# scd55104_chess_clock.net
KiCad netlist of a schematic drawn in EAGLE
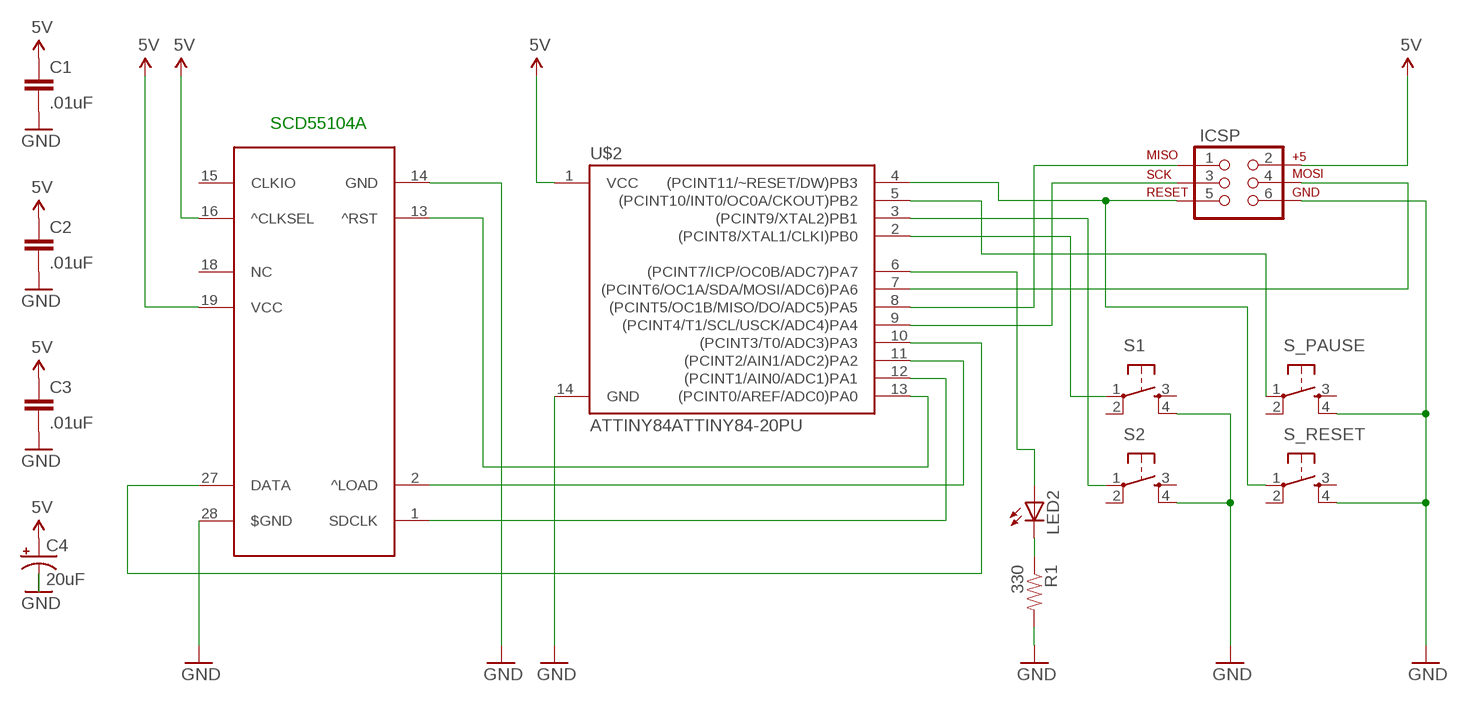
[diagram p0: schematic, sheet 1]

(export (version "E")
  (design (tool "Eeschema 10.0.6"))
  (components
    (comp (ref "C1")
      (value ".01uF")
      (footprint "eagle-import:CAP-PTH-SMALL")
      (libsource (lib "eagle-import") (part "CAPPTH"))
    )
    (comp (ref "C2")
      (value ".01uF")
      (footprint "eagle-import:CAP-PTH-SMALL")
      (libsource (lib "eagle-import") (part "CAPPTH"))
    )
    (comp (ref "C3")
      (value ".01uF")
      (footprint "eagle-import:CAP-PTH-SMALL")
      (libsource (lib "eagle-import") (part "CAPPTH"))
    )
    (comp (ref "C4")
      (value "20uF")
      (footprint "eagle-import:CPOL-RADIAL-10UF-25V")
      (libsource (lib "eagle-import") (part "CAP_POLPTH2"))
    )
    (comp (ref "ICSP")
      (value "AVR_SPI_PRG_6PTH")
      (footprint "eagle-import:2X3")
      (libsource (lib "eagle-import") (part "AVR_SPI_PRG_6PTH"))
    )
    (comp (ref "LED2")
      (value "LED3MM")
      (footprint "eagle-import:LED3MM")
      (libsource (lib "eagle-import") (part "LED3MM"))
    )
    (comp (ref "R1")
      (value "330")
      (footprint "eagle-import:AXIAL-0.4")
      (libsource (lib "eagle-import") (part "RESISTORPTH-1/4W"))
    )
    (comp (ref "S1")
      (value "TAC_SWITCHPTH")
      (footprint "eagle-import:TACTILE-PTH")
      (libsource (lib "eagle-import") (part "TAC_SWITCHPTH"))
    )
    (comp (ref "S2")
      (value "TAC_SWITCHPTH")
      (footprint "eagle-import:TACTILE-PTH")
      (libsource (lib "eagle-import") (part "TAC_SWITCHPTH"))
    )
    (comp (ref "SCD55104A")
      (value "SCD_55104A")
      (footprint "eagle-import:SCD55104A")
      (libsource (lib "eagle-import") (part "SCD_55104A"))
    )
    (comp (ref "S_PAUSE")
      (value "TAC_SWITCHPTH")
      (footprint "eagle-import:TACTILE-PTH")
      (libsource (lib "eagle-import") (part "TAC_SWITCHPTH"))
    )
    (comp (ref "S_RESET")
      (value "TAC_SWITCHPTH")
      (footprint "eagle-import:TACTILE-PTH")
      (libsource (lib "eagle-import") (part "TAC_SWITCHPTH"))
    )
    (comp (ref "U$2")
      (value "ATTINY84ATTINY84-20PU")
      (footprint "eagle-import:DIL14")
      (libsource (lib "eagle-import") (part "ATTINY84ATTINY84-20PU"))
    )
  )
  (nets
    (net (code "1") (name "5V") (class "Default")
      (node (ref "C1") (pin "1") (pinfunction "1_1") (pintype "passive"))
      (node (ref "C2") (pin "1") (pinfunction "1_1") (pintype "passive"))
      (node (ref "C3") (pin "1") (pinfunction "1_1") (pintype "passive"))
      (node (ref "C4") (pin "1") (pinfunction "+_1") (pintype "passive"))
      (node (ref "ICSP") (pin "2") (pinfunction "2_2") (pintype "passive"))
      (node (ref "SCD55104A") (pin "16") (pinfunction "^CLKSEL_16") (pintype "bidirectional"))
      (node (ref "SCD55104A") (pin "19") (pinfunction "VCC_19") (pintype "bidirectional"))
      (node (ref "U$2") (pin "1") (pinfunction "VCC_1") (pintype "bidirectional"))
    )
    (net (code "2") (name "GND") (class "Default")
      (node (ref "C1") (pin "2") (pinfunction "2_2") (pintype "passive"))
      (node (ref "C2") (pin "2") (pinfunction "2_2") (pintype "passive"))
      (node (ref "C3") (pin "2") (pinfunction "2_2") (pintype "passive"))
      (node (ref "C4") (pin "2") (pinfunction "-_2") (pintype "passive"))
      (node (ref "ICSP") (pin "6") (pinfunction "6_6") (pintype "passive"))
      (node (ref "R1") (pin "P$2") (pinfunction "2_P$2") (pintype "passive"))
      (node (ref "S1") (pin "4") (pinfunction "4_4") (pintype "passive"))
      (node (ref "S2") (pin "4") (pinfunction "4_4") (pintype "passive"))
      (node (ref "SCD55104A") (pin "14") (pinfunction "GND_14") (pintype "bidirectional"))
      (node (ref "SCD55104A") (pin "28") (pinfunction "$GND_28") (pintype "bidirectional"))
      (node (ref "S_PAUSE") (pin "4") (pinfunction "4_4") (pintype "passive"))
      (node (ref "S_RESET") (pin "4") (pinfunction "4_4") (pintype "passive"))
      (node (ref "U$2") (pin "14") (pinfunction "GND_14") (pintype "bidirectional"))
    )
    (net (code "3") (name "Net-(LED2-C)") (class "Default")
      (node (ref "LED2") (pin "K") (pinfunction "C_K") (pintype "passive"))
      (node (ref "R1") (pin "P$1") (pinfunction "1_P$1") (pintype "passive"))
    )
    (net (code "4") (name "Net-(SCD55104A-DATA)") (class "Default")
      (node (ref "SCD55104A") (pin "27") (pinfunction "DATA_27") (pintype "bidirectional"))
      (node (ref "U$2") (pin "10") (pinfunction "(PCINT3/T0/ADC3)PA3_10") (pintype "bidirectional"))
    )
    (net (code "5") (name "Net-(SCD55104A-SDCLK)") (class "Default")
      (node (ref "SCD55104A") (pin "1") (pinfunction "SDCLK_1") (pintype "bidirectional"))
      (node (ref "U$2") (pin "12") (pinfunction "(PCINT1/AIN0/ADC1)PA1_12") (pintype "bidirectional"))
    )
    (net (code "6") (name "Net-(SCD55104A-^LOAD)") (class "Default")
      (node (ref "SCD55104A") (pin "2") (pinfunction "^LOAD_2") (pintype "bidirectional"))
      (node (ref "U$2") (pin "11") (pinfunction "(PCINT2/AIN1/ADC2)PA2_11") (pintype "bidirectional"))
    )
    (net (code "7") (name "Net-(SCD55104A-^RST)") (class "Default")
      (node (ref "SCD55104A") (pin "13") (pinfunction "^RST_13") (pintype "bidirectional"))
      (node (ref "U$2") (pin "13") (pinfunction "(PCINT0/AREF/ADC0)PA0_13") (pintype "bidirectional"))
    )
    (net (code "8") (name "Net-(U$2-(PCINT4{slash}T1{slash}SCL{slash}USCK{slash}ADC4)PA4)") (class "Default")
      (node (ref "ICSP") (pin "3") (pinfunction "3_3") (pintype "passive"))
      (node (ref "U$2") (pin "9") (pinfunction "(PCINT4/T1/SCL/USCK/ADC4)PA4_9") (pintype "bidirectional"))
    )
    (net (code "9") (name "Net-(U$2-(PCINT5{slash}OC1B{slash}MISO{slash}DO{slash}ADC5)PA5)") (class "Default")
      (node (ref "ICSP") (pin "1") (pinfunction "1_1") (pintype "passive"))
      (node (ref "U$2") (pin "8") (pinfunction "(PCINT5/OC1B/MISO/DO/ADC5)PA5_8") (pintype "bidirectional"))
    )
    (net (code "10") (name "Net-(U$2-(PCINT6{slash}OC1A{slash}SDA{slash}MOSI{slash}ADC6)PA6)") (class "Default")
      (node (ref "ICSP") (pin "4") (pinfunction "4_4") (pintype "passive"))
      (node (ref "U$2") (pin "7") (pinfunction "(PCINT6/OC1A/SDA/MOSI/ADC6)PA6_7") (pintype "bidirectional"))
    )
    (net (code "11") (name "Net-(U$2-(PCINT7{slash}ICP{slash}OC0B{slash}ADC7)PA7)") (class "Default")
      (node (ref "LED2") (pin "A") (pinfunction "A_A") (pintype "passive"))
      (node (ref "U$2") (pin "6") (pinfunction "(PCINT7/ICP/OC0B/ADC7)PA7_6") (pintype "bidirectional"))
    )
    (net (code "12") (name "Net-(U$2-(PCINT8{slash}XTAL1{slash}CLKI)PB0)") (class "Default")
      (node (ref "S1") (pin "1") (pinfunction "1_1") (pintype "passive"))
      (node (ref "U$2") (pin "2") (pinfunction "(PCINT8/XTAL1/CLKI)PB0_2") (pintype "bidirectional"))
    )
    (net (code "13") (name "Net-(U$2-(PCINT9{slash}XTAL2)PB1)") (class "Default")
      (node (ref "S2") (pin "1") (pinfunction "1_1") (pintype "passive"))
      (node (ref "U$2") (pin "3") (pinfunction "(PCINT9/XTAL2)PB1_3") (pintype "bidirectional"))
    )
    (net (code "14") (name "Net-(U$2-(PCINT10{slash}INT0{slash}OC0A{slash}CKOUT)PB2)") (class "Default")
      (node (ref "S_PAUSE") (pin "1") (pinfunction "1_1") (pintype "passive"))
      (node (ref "U$2") (pin "5") (pinfunction "(PCINT10/INT0/OC0A/CKOUT)PB2_5") (pintype "bidirectional"))
    )
    (net (code "15") (name "Net-(U$2-(PCINT11{slash}~{RESET{slash}DW})PB3)") (class "Default")
      (node (ref "ICSP") (pin "5") (pinfunction "5_5") (pintype "passive"))
      (node (ref "S_RESET") (pin "1") (pinfunction "1_1") (pintype "passive"))
      (node (ref "U$2") (pin "4") (pinfunction "(PCINT11/~{RESET/DW})PB3_4") (pintype "bidirectional"))
    )
    (net (code "16") (name "unconnected-(S1-Pad2)") (class "Default")
      (node (ref "S1") (pin "2") (pinfunction "2_2") (pintype "passive"))
    )
    (net (code "17") (name "unconnected-(S1-Pad3)") (class "Default")
      (node (ref "S1") (pin "3") (pinfunction "3_3") (pintype "passive"))
    )
    (net (code "18") (name "unconnected-(S2-Pad2)") (class "Default")
      (node (ref "S2") (pin "2") (pinfunction "2_2") (pintype "passive"))
    )
    (net (code "19") (name "unconnected-(S2-Pad3)") (class "Default")
      (node (ref "S2") (pin "3") (pinfunction "3_3") (pintype "passive"))
    )
    (net (code "20") (name "unconnected-(SCD55104A-CLKIO-Pad15)") (class "Default")
      (node (ref "SCD55104A") (pin "15") (pinfunction "CLKIO_15") (pintype "bidirectional"))
    )
    (net (code "21") (name "unconnected-(SCD55104A-NC-Pad18)") (class "Default")
      (node (ref "SCD55104A") (pin "18") (pinfunction "NC_18") (pintype "bidirectional"))
    )
    (net (code "22") (name "unconnected-(S_PAUSE-Pad2)") (class "Default")
      (node (ref "S_PAUSE") (pin "2") (pinfunction "2_2") (pintype "passive"))
    )
    (net (code "23") (name "unconnected-(S_PAUSE-Pad3)") (class "Default")
      (node (ref "S_PAUSE") (pin "3") (pinfunction "3_3") (pintype "passive"))
    )
    (net (code "24") (name "unconnected-(S_RESET-Pad2)") (class "Default")
      (node (ref "S_RESET") (pin "2") (pinfunction "2_2") (pintype "passive"))
    )
    (net (code "25") (name "unconnected-(S_RESET-Pad3)") (class "Default")
      (node (ref "S_RESET") (pin "3") (pinfunction "3_3") (pintype "passive"))
    )
  )
)
